# QPB-V1.net
KiCad netlist of a schematic drawn in Altium Designer
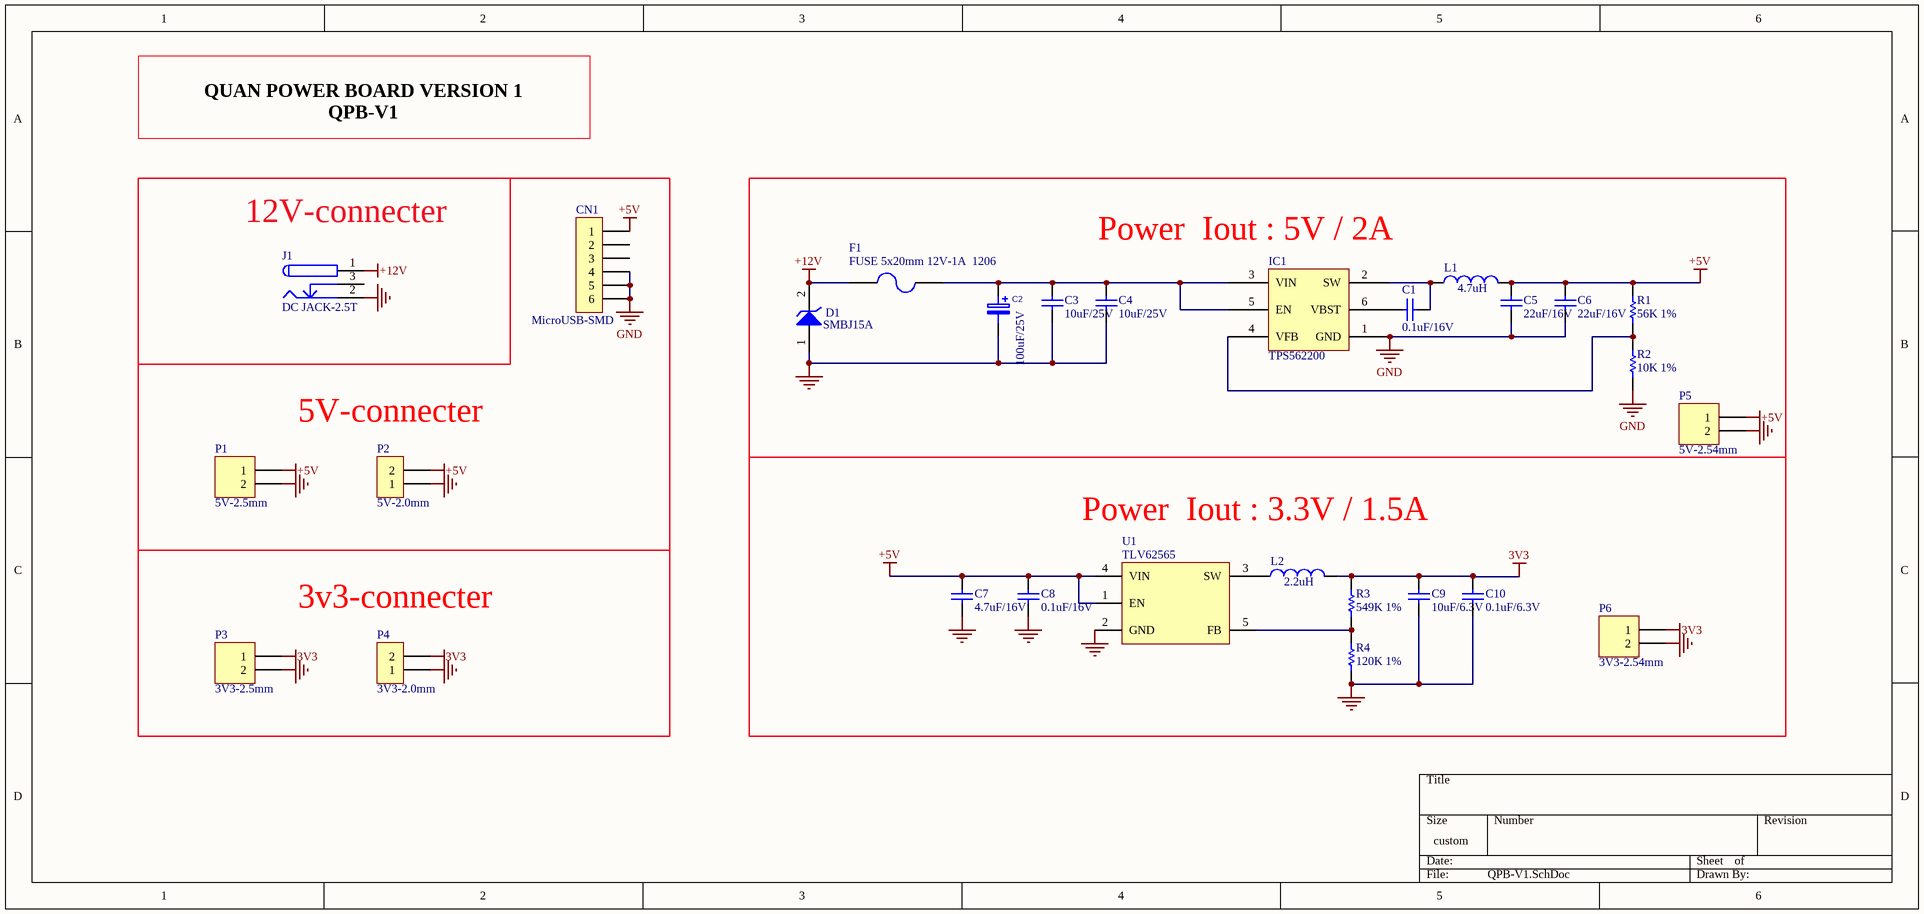
[diagram p0: QPB-V1.SchDoc]

(export (version "E")
  (design (tool "Eeschema 10.0.6"))
  (components
    (comp (ref "C1")
      (value "0.1uF/16V")
      (footprint "0603C")
      (description "Capacitor (Semiconductor SIM Model)")
      (fields (field (name "PUBLISHER") "Altium Limited"))
      (libsource (lib "*") (part "Cap Semi"))
    )
    (comp (ref "C2")
      (value "100uF/25V")
      (footprint "DIP CAP-6.5*2.54")
      (fields
        (field (name "PART NUMBER") "53300833000")
        (field (name "TOLERANCE") "20%")
        (field (name "VALUE_ALLEGRO") "100uF/25V")
      )
      (libsource (lib "*") (part "C POL"))
    )
    (comp (ref "C3")
      (value "10uF/25V")
      (footprint "0603C")
      (description "Capacitor (Semiconductor SIM Model)")
      (fields (field (name "PUBLISHER") "Altium Limited"))
      (libsource (lib "*") (part "Cap Semi"))
    )
    (comp (ref "C4")
      (value "10uF/25V")
      (footprint "0603C")
      (description "Capacitor (Semiconductor SIM Model)")
      (fields (field (name "PUBLISHER") "Altium Limited"))
      (libsource (lib "*") (part "Cap Semi"))
    )
    (comp (ref "C5")
      (value "22uF/16V")
      (footprint "0603C")
      (description "Capacitor (Semiconductor SIM Model)")
      (fields (field (name "PUBLISHER") "Altium Limited"))
      (libsource (lib "*") (part "Cap Semi"))
    )
    (comp (ref "C6")
      (value "22uF/16V")
      (footprint "0603C")
      (description "Capacitor (Semiconductor SIM Model)")
      (fields (field (name "PUBLISHER") "Altium Limited"))
      (libsource (lib "*") (part "Cap Semi"))
    )
    (comp (ref "C7")
      (value "4.7uF/16V")
      (footprint "0603C")
      (description "Capacitor (Semiconductor SIM Model)")
      (fields (field (name "PUBLISHER") "Altium Limited"))
      (libsource (lib "*") (part "Cap Semi"))
    )
    (comp (ref "C8")
      (value "0.1uF/16V")
      (footprint "0603C")
      (description "Capacitor (Semiconductor SIM Model)")
      (fields (field (name "PUBLISHER") "Altium Limited"))
      (libsource (lib "*") (part "Cap Semi"))
    )
    (comp (ref "C9")
      (value "10uF/6.3V")
      (footprint "0603C")
      (description "Capacitor (Semiconductor SIM Model)")
      (fields (field (name "PUBLISHER") "Altium Limited"))
      (libsource (lib "*") (part "Cap Semi"))
    )
    (comp (ref "C10")
      (value "0.1uF/6.3V")
      (footprint "0603C")
      (description "Capacitor (Semiconductor SIM Model)")
      (fields (field (name "PUBLISHER") "Altium Limited"))
      (libsource (lib "*") (part "Cap Semi"))
    )
    (comp (ref "CN1")
      (value "MicroUSB-SMD")
      (footprint "USB--MICRO-WMRU2-05FLBSRF")
      (description "Connector")
      (libsource (lib "*") (part "CON6"))
    )
    (comp (ref "D1")
      (value "SMBJ15A")
      (footprint "SMBJ40CA(TVS)")
      (description "Zener Diode")
      (libsource (lib "*") (part "PESD5V0L1BA"))
    )
    (comp (ref "F1")
      (value "FUSE 5x20mm 12V-1A  1206")
      (footprint "1206-FUSE")
      (description "Fuse")
      (libsource (lib "*") (part "FUSE2"))
    )
    (comp (ref "IC1")
      (value "TPS562200")
      (footprint "SOT-23-6-0.95mm")
      (libsource (lib "*") (part "Tps562200"))
    )
    (comp (ref "J1")
      (value "DC JACK-2.5T")
      (footprint "DC JACK-2.5T-NEW")
      (description "Low Voltage Power Supply Connector")
      (fields (field (name "PUBLISHER") "*"))
      (libsource (lib "*") (part "DCJACK-1"))
    )
    (comp (ref "L1")
      (value "4.7uH")
      (footprint "L3X3.5")
      (description "Inductor")
      (fields (field (name "PUBLISHER") "Altium Limited"))
      (libsource (lib "*") (part "Inductor"))
    )
    (comp (ref "L2") (value "2.2uH") (footprint "L3X3.5") (libsource (lib "OTHNER") (part "L")))
    (comp (ref "P1")
      (value "5V-2.5mm")
      (footprint "WHITEWAFER2-25")
      (description "Header, 2-Pin")
      (fields (field (name "PUBLISHER") "Altium Limited"))
      (libsource (lib "Miscellaneous Connectors") (part "Header 2"))
    )
    (comp (ref "P2")
      (value "5V-2.0mm")
      (footprint "WHITEWAFER2-200")
      (description "Connector")
      (libsource (lib "PIN") (part "2PIN-200"))
    )
    (comp (ref "P3")
      (value "3V3-2.5mm")
      (footprint "WHITEWAFER2-25")
      (description "Header, 2-Pin")
      (fields (field (name "PUBLISHER") "Altium Limited"))
      (libsource (lib "Miscellaneous Connectors") (part "Header 2"))
    )
    (comp (ref "P4")
      (value "3V3-2.0mm")
      (footprint "WHITEWAFER2-200")
      (description "Connector")
      (libsource (lib "PIN") (part "2PIN-200"))
    )
    (comp (ref "P5")
      (value "5V-2.54mm")
      (footprint "HDR1X2")
      (description "Header, 2-Pin")
      (fields (field (name "PUBLISHER") "Altium Limited"))
      (libsource (lib "Miscellaneous Connectors") (part "Header 2"))
    )
    (comp (ref "P6")
      (value "3V3-2.54mm")
      (footprint "HDR1X2")
      (description "Header, 2-Pin")
      (fields (field (name "PUBLISHER") "Altium Limited"))
      (libsource (lib "Miscellaneous Connectors") (part "Header 2"))
    )
    (comp (ref "R1")
      (value "56K 1%")
      (footprint "0603")
      (description "Semiconductor Resistor")
      (fields (field (name "PUBLISHER") "Altium Limited"))
      (libsource (lib "*") (part "Res Semi"))
    )
    (comp (ref "R2")
      (value "10K 1%")
      (footprint "0603")
      (description "Semiconductor Resistor")
      (fields (field (name "PUBLISHER") "Altium Limited"))
      (libsource (lib "*") (part "Res Semi"))
    )
    (comp (ref "R3")
      (value "549K 1%")
      (footprint "0603")
      (description "Semiconductor Resistor")
      (fields (field (name "PUBLISHER") "Altium Limited"))
      (libsource (lib "*") (part "Res Semi"))
    )
    (comp (ref "R4")
      (value "120K 1%")
      (footprint "0603")
      (description "Semiconductor Resistor")
      (fields (field (name "PUBLISHER") "Altium Limited"))
      (libsource (lib "*") (part "Res Semi"))
    )
    (comp (ref "U1") (value "TLV62565") (footprint "SOT-23-5-0.95MM") (libsource (lib "IC") (part "TL62565")))
  )
  (nets
    (net (code "1") (name "+5V") (class "Default")
      (node (ref "C5") (pin "2") (pinfunction "2_2") (pintype "passive"))
      (node (ref "C6") (pin "2") (pinfunction "2_2") (pintype "passive"))
      (node (ref "C7") (pin "2") (pinfunction "2_2") (pintype "passive"))
      (node (ref "C8") (pin "2") (pinfunction "2_2") (pintype "passive"))
      (node (ref "CN1") (pin "1") (pinfunction "1_1") (pintype "passive"))
      (node (ref "L1") (pin "2") (pinfunction "2_2") (pintype "passive"))
      (node (ref "P1") (pin "1") (pinfunction "1_1") (pintype "passive"))
      (node (ref "P2") (pin "2") (pinfunction "2_2") (pintype "passive"))
      (node (ref "P5") (pin "1") (pinfunction "1_1") (pintype "passive"))
      (node (ref "R1") (pin "2") (pinfunction "2_2") (pintype "passive"))
      (node (ref "U1") (pin "1") (pinfunction "EN_1") (pintype "passive"))
      (node (ref "U1") (pin "4") (pinfunction "VIN_4") (pintype "passive"))
    )
    (net (code "2") (name "+12V") (class "Default")
      (node (ref "D1") (pin "2") (pinfunction "2_2") (pintype "passive"))
      (node (ref "F1") (pin "1") (pinfunction "1_1") (pintype "passive"))
      (node (ref "J1") (pin "1") (pinfunction "1_1") (pintype "power_in"))
    )
    (net (code "3") (name "3V3") (class "Default")
      (node (ref "C10") (pin "2") (pinfunction "2_2") (pintype "passive"))
      (node (ref "C9") (pin "2") (pinfunction "2_2") (pintype "passive"))
      (node (ref "L2") (pin "2") (pinfunction "2_2") (pintype "passive"))
      (node (ref "P3") (pin "1") (pinfunction "1_1") (pintype "passive"))
      (node (ref "P4") (pin "2") (pinfunction "2_2") (pintype "passive"))
      (node (ref "P6") (pin "1") (pinfunction "1_1") (pintype "passive"))
      (node (ref "R3") (pin "2") (pinfunction "2_2") (pintype "passive"))
    )
    (net (code "4") (name "GND") (class "Default")
      (node (ref "C10") (pin "1") (pinfunction "1_1") (pintype "passive"))
      (node (ref "C2") (pin "2") (pinfunction "2_2") (pintype "passive"))
      (node (ref "C3") (pin "1") (pinfunction "1_1") (pintype "passive"))
      (node (ref "C4") (pin "1") (pinfunction "1_1") (pintype "passive"))
      (node (ref "C5") (pin "1") (pinfunction "1_1") (pintype "passive"))
      (node (ref "C6") (pin "1") (pinfunction "1_1") (pintype "passive"))
      (node (ref "C7") (pin "1") (pinfunction "1_1") (pintype "passive"))
      (node (ref "C8") (pin "1") (pinfunction "1_1") (pintype "passive"))
      (node (ref "C9") (pin "1") (pinfunction "1_1") (pintype "passive"))
      (node (ref "CN1") (pin "4") (pinfunction "4_4") (pintype "passive"))
      (node (ref "CN1") (pin "5") (pinfunction "5_5") (pintype "passive"))
      (node (ref "CN1") (pin "6") (pinfunction "6_6") (pintype "passive"))
      (node (ref "D1") (pin "1") (pinfunction "1_1") (pintype "passive"))
      (node (ref "IC1") (pin "1") (pinfunction "GND_1") (pintype "passive"))
      (node (ref "J1") (pin "2") (pinfunction "2_2") (pintype "power_in"))
      (node (ref "P1") (pin "2") (pinfunction "2_2") (pintype "passive"))
      (node (ref "P2") (pin "1") (pinfunction "1_1") (pintype "passive"))
      (node (ref "P3") (pin "2") (pinfunction "2_2") (pintype "passive"))
      (node (ref "P4") (pin "1") (pinfunction "1_1") (pintype "passive"))
      (node (ref "P5") (pin "2") (pinfunction "2_2") (pintype "passive"))
      (node (ref "P6") (pin "2") (pinfunction "2_2") (pintype "passive"))
      (node (ref "R2") (pin "1") (pinfunction "1_1") (pintype "passive"))
      (node (ref "R4") (pin "1") (pinfunction "1_1") (pintype "passive"))
      (node (ref "U1") (pin "2") (pinfunction "GND_2") (pintype "passive"))
    )
    (net (code "5") (name "Net-(IC1-EN)") (class "Default")
      (node (ref "C2") (pin "1") (pinfunction "1_1") (pintype "passive"))
      (node (ref "C3") (pin "2") (pinfunction "2_2") (pintype "passive"))
      (node (ref "C4") (pin "2") (pinfunction "2_2") (pintype "passive"))
      (node (ref "F1") (pin "2") (pinfunction "2_2") (pintype "passive"))
      (node (ref "IC1") (pin "3") (pinfunction "VIN_3") (pintype "passive"))
      (node (ref "IC1") (pin "5") (pinfunction "EN_5") (pintype "passive"))
    )
    (net (code "6") (name "Net-(IC1-SW)") (class "Default")
      (node (ref "C1") (pin "1") (pinfunction "1_1") (pintype "passive"))
      (node (ref "IC1") (pin "2") (pinfunction "SW_2") (pintype "passive"))
      (node (ref "L1") (pin "1") (pinfunction "1_1") (pintype "passive"))
    )
    (net (code "7") (name "Net-(IC1-VBST)") (class "Default")
      (node (ref "C1") (pin "2") (pinfunction "2_2") (pintype "passive"))
      (node (ref "IC1") (pin "6") (pinfunction "VBST_6") (pintype "passive"))
    )
    (net (code "8") (name "Net-(IC1-VFB)") (class "Default")
      (node (ref "IC1") (pin "4") (pinfunction "VFB_4") (pintype "passive"))
      (node (ref "R1") (pin "1") (pinfunction "1_1") (pintype "passive"))
      (node (ref "R2") (pin "2") (pinfunction "2_2") (pintype "passive"))
    )
    (net (code "9") (name "Net-(U1-FB)") (class "Default")
      (node (ref "R3") (pin "1") (pinfunction "1_1") (pintype "passive"))
      (node (ref "R4") (pin "2") (pinfunction "2_2") (pintype "passive"))
      (node (ref "U1") (pin "5") (pinfunction "FB_5") (pintype "passive"))
    )
    (net (code "10") (name "Net-(U1-SW)") (class "Default")
      (node (ref "L2") (pin "1") (pinfunction "1_1") (pintype "passive"))
      (node (ref "U1") (pin "3") (pinfunction "SW_3") (pintype "passive"))
    )
    (net (code "11") (name "unconnected-(CN1-Pad2)") (class "Default")
      (node (ref "CN1") (pin "2") (pinfunction "2_2") (pintype "passive"))
    )
    (net (code "12") (name "unconnected-(CN1-Pad3)") (class "Default")
      (node (ref "CN1") (pin "3") (pinfunction "3_3") (pintype "passive"))
    )
    (net (code "13") (name "unconnected-(J1-Pad3)") (class "Default")
      (node (ref "J1") (pin "3") (pinfunction "3_3") (pintype "power_in"))
    )
  )
)
